# transmitter.net
KiCad netlist of a schematic drawn in EAGLE
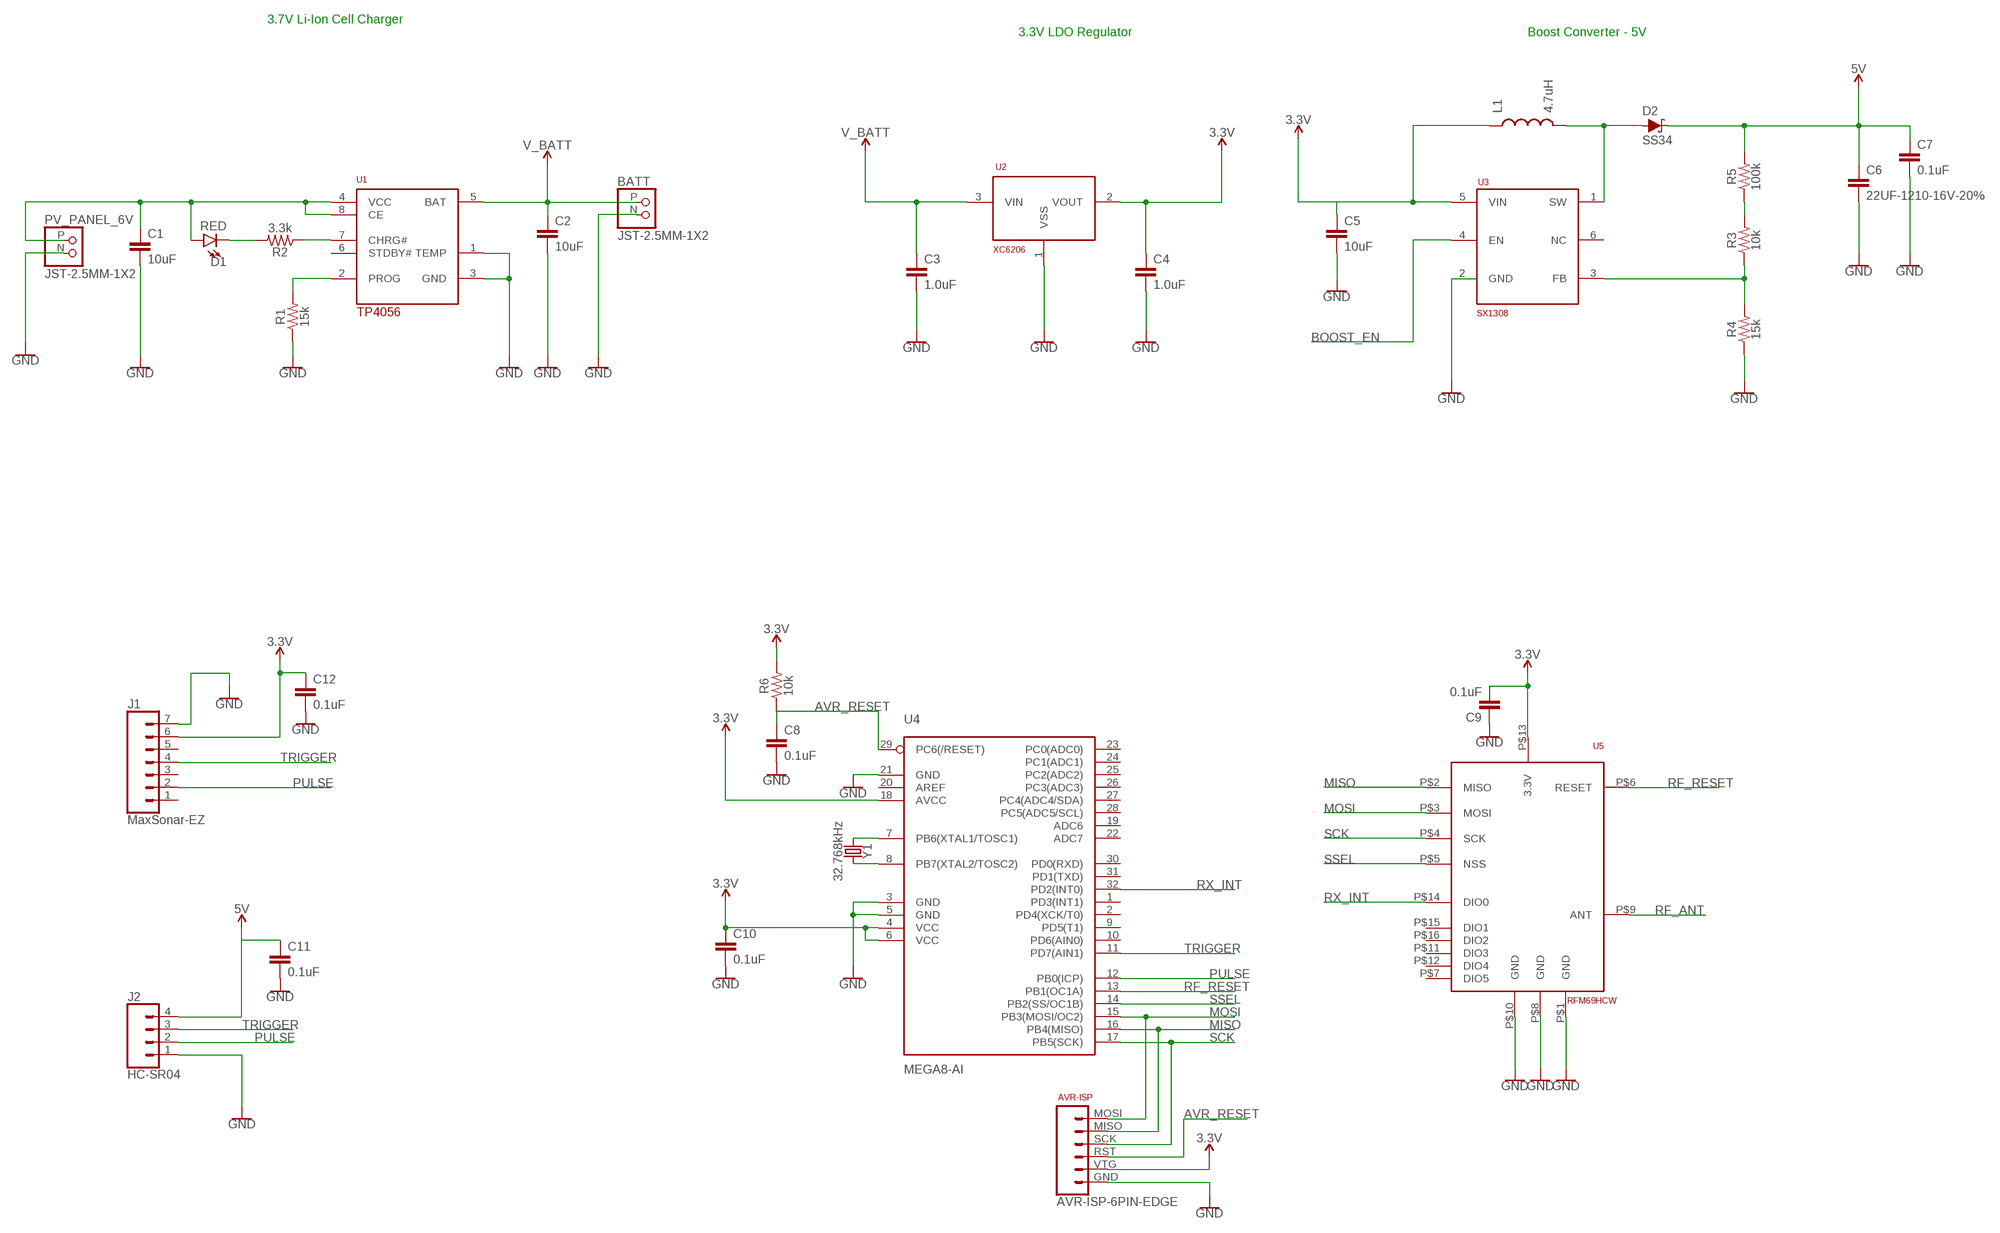
[diagram p0: schematic, sheet 1]

(export (version "E")
  (design (tool "Eeschema 10.0.6"))
  (components
    (comp (ref "BATT")
      (value "JST-2.5MM-1X2")
      (footprint "eagle-import:JST-2.5MM-1X2-THM")
      (libsource (lib "eagle-import") (part "JST-2.5MM-1X2"))
    )
    (comp (ref "C1")
      (value "10uF")
      (footprint "eagle-import:1206")
      (libsource (lib "eagle-import") (part "10UF-1206-6.3V-20%"))
    )
    (comp (ref "C2")
      (value "10uF")
      (footprint "eagle-import:1206")
      (libsource (lib "eagle-import") (part "10UF-1206-6.3V-20%"))
    )
    (comp (ref "C3")
      (value "1.0uF")
      (footprint "eagle-import:0603")
      (libsource (lib "eagle-import") (part "1.0UF-0603-16V-10%"))
    )
    (comp (ref "C4")
      (value "1.0uF")
      (footprint "eagle-import:0603")
      (libsource (lib "eagle-import") (part "1.0UF-0603-16V-10%"))
    )
    (comp (ref "C5")
      (value "10uF")
      (footprint "eagle-import:1206")
      (libsource (lib "eagle-import") (part "10UF-1206-6.3V-20%"))
    )
    (comp (ref "C6")
      (value "22UF-1210-16V-20%")
      (footprint "eagle-import:1210")
      (libsource (lib "eagle-import") (part "22UF-1210-16V-20%"))
    )
    (comp (ref "C7")
      (value "0.1uF")
      (footprint "eagle-import:0603")
      (libsource (lib "eagle-import") (part "0.1UF-0603-25V-5%"))
    )
    (comp (ref "C8")
      (value "0.1uF")
      (footprint "eagle-import:0603")
      (libsource (lib "eagle-import") (part "0.1UF-0603-25V-5%"))
    )
    (comp (ref "C9")
      (value "0.1uF")
      (footprint "eagle-import:0603")
      (libsource (lib "eagle-import") (part "0.1UF-0603-25V-(+80/-20%)"))
    )
    (comp (ref "C10")
      (value "0.1uF")
      (footprint "eagle-import:0603")
      (libsource (lib "eagle-import") (part "0.1UF-0603-25V-(+80/-20%)"))
    )
    (comp (ref "C11")
      (value "0.1uF")
      (footprint "eagle-import:0603")
      (libsource (lib "eagle-import") (part "0.1UF-0603-25V-(+80/-20%)"))
    )
    (comp (ref "C12")
      (value "0.1uF")
      (footprint "eagle-import:0603")
      (libsource (lib "eagle-import") (part "0.1UF-0603-25V-(+80/-20%)"))
    )
    (comp (ref "D1")
      (value "RED")
      (footprint "eagle-import:LED-1206")
      (libsource (lib "eagle-import") (part "LED-RED1206"))
    )
    (comp (ref "D2")
      (value "SS34")
      (footprint "eagle-import:SMA-DIODE")
      (libsource (lib "eagle-import") (part "DIODE-SCHOTTKY"))
    )
    (comp (ref "J1")
      (value "MaxSonar-EZ")
      (footprint "eagle-import:1X07")
      (libsource (lib "eagle-import") (part "CONN_07"))
    )
    (comp (ref "J2")
      (value "HC-SR04")
      (footprint "eagle-import:1X04")
      (libsource (lib "eagle-import") (part "CONN_04"))
    )
    (comp (ref "L1")
      (value "4.7uH")
      (footprint "eagle-import:SDR0403")
      (libsource (lib "eagle-import") (part "INDUCTOR3MM"))
    )
    (comp (ref "PV_PANEL_6V")
      (value "JST-2.5MM-1X2")
      (footprint "eagle-import:JST-2.5MM-1X2-THM")
      (libsource (lib "eagle-import") (part "JST-2.5MM-1X2"))
    )
    (comp (ref "R1")
      (value "15k")
      (footprint "eagle-import:0603")
      (libsource (lib "eagle-import") (part "15KOHM-0603-1/10W-1%"))
    )
    (comp (ref "R2")
      (value "3.3k")
      (footprint "eagle-import:0603")
      (libsource (lib "eagle-import") (part "3.3KOHM-0603-1/10W-1%"))
    )
    (comp (ref "R3")
      (value "10k")
      (footprint "eagle-import:0603")
      (libsource (lib "eagle-import") (part "10KOHM-0603-1/10W-1%"))
    )
    (comp (ref "R4")
      (value "15k")
      (footprint "eagle-import:0603")
      (libsource (lib "eagle-import") (part "15KOHM-0603-1/10W-1%"))
    )
    (comp (ref "R5")
      (value "100k")
      (footprint "eagle-import:0603")
      (libsource (lib "eagle-import") (part "100KOHM-0603-1/10W-1%"))
    )
    (comp (ref "R6")
      (value "10k")
      (footprint "eagle-import:0603")
      (libsource (lib "eagle-import") (part "10KOHM-0603-1/10W-1%"))
    )
    (comp (ref "U$3")
      (value "AVR-ISP-6PIN-EDGE")
      (footprint "eagle-import:AVR-6PIN-ISP-EDGE")
      (libsource (lib "eagle-import") (part "AVR-ISP-6PIN-EDGE"))
    )
    (comp (ref "U1")
      (value "TP4056")
      (footprint "eagle-import:SO08")
      (libsource (lib "eagle-import") (part "TP4056"))
    )
    (comp (ref "U2")
      (value "XC6206")
      (footprint "eagle-import:SOT23-3")
      (libsource (lib "eagle-import") (part "XC6206"))
    )
    (comp (ref "U3")
      (value "SX1308")
      (footprint "eagle-import:SOT23-6")
      (libsource (lib "eagle-import") (part "SX1308"))
    )
    (comp (ref "U4")
      (value "MEGA8-AI")
      (footprint "eagle-import:TQFP32-08")
      (fields (field (name "MPN") "ATMEGA8-16AU"))
      (libsource (lib "eagle-import") (part "MEGA8-AI"))
    )
    (comp (ref "U5")
      (value "RFM69HCW")
      (footprint "eagle-import:RFM69HCW")
      (libsource (lib "eagle-import") (part "RFM69HCW"))
    )
    (comp (ref "Y1")
      (value "32.768kHz")
      (footprint "eagle-import:CRYSTAL-PTH-2X6-CYL")
      (libsource (lib "eagle-import") (part "CRYSTAL-32.768KHZPTH-2X6"))
    )
  )
  (nets
    (net (code "1") (name "/AVR_RESET") (class "Default")
      (node (ref "C8") (pin "1") (pinfunction "1_1") (pintype "passive"))
      (node (ref "R6") (pin "1") (pinfunction "1_1") (pintype "passive"))
      (node (ref "U$3") (pin "RST") (pinfunction "RST_RST") (pintype "passive"))
      (node (ref "U4") (pin "29") (pinfunction "PC6(/RESET)_29") (pintype "bidirectional"))
    )
    (net (code "2") (name "/BOOST_EN") (class "Default")
      (node (ref "U3") (pin "4") (pinfunction "EN_4") (pintype "bidirectional"))
    )
    (net (code "3") (name "/MISO") (class "Default")
      (node (ref "U$3") (pin "MISO") (pinfunction "MISO_MISO") (pintype "passive"))
      (node (ref "U4") (pin "16") (pinfunction "PB4(MISO)_16") (pintype "bidirectional"))
      (node (ref "U5") (pin "P$2") (pinfunction "MISO_P$2") (pintype "bidirectional"))
    )
    (net (code "4") (name "/MOSI") (class "Default")
      (node (ref "U$3") (pin "MOSI") (pinfunction "MOSI_MOSI") (pintype "passive"))
      (node (ref "U4") (pin "15") (pinfunction "PB3(MOSI/OC2)_15") (pintype "bidirectional"))
      (node (ref "U5") (pin "P$3") (pinfunction "MOSI_P$3") (pintype "bidirectional"))
    )
    (net (code "5") (name "/PULSE") (class "Default")
      (node (ref "J1") (pin "2") (pinfunction "2_2") (pintype "passive"))
      (node (ref "J2") (pin "2") (pinfunction "2_2") (pintype "passive"))
      (node (ref "U4") (pin "12") (pinfunction "PB0(ICP)_12") (pintype "bidirectional"))
    )
    (net (code "6") (name "/RF_ANT") (class "Default")
      (node (ref "U5") (pin "P$9") (pinfunction "ANT_P$9") (pintype "bidirectional"))
    )
    (net (code "7") (name "/RF_RESET") (class "Default")
      (node (ref "U4") (pin "13") (pinfunction "PB1(OC1A)_13") (pintype "bidirectional"))
      (node (ref "U5") (pin "P$6") (pinfunction "RESET_P$6") (pintype "bidirectional"))
    )
    (net (code "8") (name "/RX_INT") (class "Default")
      (node (ref "U4") (pin "32") (pinfunction "PD2(INT0)_32") (pintype "bidirectional"))
      (node (ref "U5") (pin "P$14") (pinfunction "DIO0_P$14") (pintype "bidirectional"))
    )
    (net (code "9") (name "/SCK") (class "Default")
      (node (ref "U$3") (pin "SCK") (pinfunction "SCK_SCK") (pintype "passive"))
      (node (ref "U4") (pin "17") (pinfunction "PB5(SCK)_17") (pintype "bidirectional"))
      (node (ref "U5") (pin "P$4") (pinfunction "SCK_P$4") (pintype "bidirectional"))
    )
    (net (code "10") (name "/SSEL") (class "Default")
      (node (ref "U4") (pin "14") (pinfunction "PB2(SS/OC1B)_14") (pintype "bidirectional"))
      (node (ref "U5") (pin "P$5") (pinfunction "NSS_P$5") (pintype "bidirectional"))
    )
    (net (code "11") (name "/TRIGGER") (class "Default")
      (node (ref "J1") (pin "4") (pinfunction "4_4") (pintype "passive"))
      (node (ref "J2") (pin "3") (pinfunction "3_3") (pintype "passive"))
      (node (ref "U4") (pin "11") (pinfunction "PD7(AIN1)_11") (pintype "bidirectional"))
    )
    (net (code "12") (name "3.3V") (class "Default")
      (node (ref "C10") (pin "1") (pinfunction "1_1") (pintype "passive"))
      (node (ref "C12") (pin "1") (pinfunction "1_1") (pintype "passive"))
      (node (ref "C4") (pin "1") (pinfunction "1_1") (pintype "passive"))
      (node (ref "C5") (pin "1") (pinfunction "1_1") (pintype "passive"))
      (node (ref "C9") (pin "2") (pinfunction "2_2") (pintype "passive"))
      (node (ref "J1") (pin "6") (pinfunction "6_6") (pintype "passive"))
      (node (ref "L1") (pin "P$1") (pinfunction "1_P$1") (pintype "passive"))
      (node (ref "R6") (pin "2") (pinfunction "2_2") (pintype "passive"))
      (node (ref "U$3") (pin "VTG") (pinfunction "VTG_VTG") (pintype "passive"))
      (node (ref "U2") (pin "2") (pinfunction "VOUT_2") (pintype "bidirectional"))
      (node (ref "U3") (pin "5") (pinfunction "VIN_5") (pintype "bidirectional"))
      (node (ref "U4") (pin "18") (pinfunction "AVCC_18") (pintype "power_in"))
      (node (ref "U4") (pin "4") (pinfunction "VCC_4") (pintype "power_in"))
      (node (ref "U4") (pin "6") (pinfunction "VCC_6") (pintype "power_in"))
      (node (ref "U5") (pin "P$13") (pinfunction "3.3V_P$13") (pintype "power_in"))
    )
    (net (code "13") (name "5V") (class "Default")
      (node (ref "C11") (pin "1") (pinfunction "1_1") (pintype "passive"))
      (node (ref "C6") (pin "1") (pinfunction "1_1") (pintype "passive"))
      (node (ref "C7") (pin "1") (pinfunction "1_1") (pintype "passive"))
      (node (ref "D2") (pin "C") (pinfunction "C_C") (pintype "passive"))
      (node (ref "J2") (pin "4") (pinfunction "4_4") (pintype "passive"))
      (node (ref "R5") (pin "2") (pinfunction "2_2") (pintype "passive"))
    )
    (net (code "14") (name "GND") (class "Default")
      (node (ref "BATT") (pin "N") (pinfunction "N_N") (pintype "passive"))
      (node (ref "C1") (pin "2") (pinfunction "2_2") (pintype "passive"))
      (node (ref "C10") (pin "2") (pinfunction "2_2") (pintype "passive"))
      (node (ref "C11") (pin "2") (pinfunction "2_2") (pintype "passive"))
      (node (ref "C12") (pin "2") (pinfunction "2_2") (pintype "passive"))
      (node (ref "C2") (pin "2") (pinfunction "2_2") (pintype "passive"))
      (node (ref "C3") (pin "2") (pinfunction "2_2") (pintype "passive"))
      (node (ref "C4") (pin "2") (pinfunction "2_2") (pintype "passive"))
      (node (ref "C5") (pin "2") (pinfunction "2_2") (pintype "passive"))
      (node (ref "C6") (pin "2") (pinfunction "2_2") (pintype "passive"))
      (node (ref "C7") (pin "2") (pinfunction "2_2") (pintype "passive"))
      (node (ref "C8") (pin "2") (pinfunction "2_2") (pintype "passive"))
      (node (ref "C9") (pin "1") (pinfunction "1_1") (pintype "passive"))
      (node (ref "J1") (pin "7") (pinfunction "7_7") (pintype "passive"))
      (node (ref "J2") (pin "1") (pinfunction "1_1") (pintype "passive"))
      (node (ref "PV_PANEL_6V") (pin "N") (pinfunction "N_N") (pintype "passive"))
      (node (ref "R1") (pin "1") (pinfunction "1_1") (pintype "passive"))
      (node (ref "R4") (pin "1") (pinfunction "1_1") (pintype "passive"))
      (node (ref "U$3") (pin "GND") (pinfunction "GND_GND") (pintype "passive"))
      (node (ref "U1") (pin "1") (pinfunction "TEMP_1") (pintype "bidirectional"))
      (node (ref "U1") (pin "3") (pinfunction "GND_3") (pintype "bidirectional"))
      (node (ref "U2") (pin "1") (pinfunction "VSS_1") (pintype "bidirectional"))
      (node (ref "U3") (pin "2") (pinfunction "GND_2") (pintype "bidirectional"))
      (node (ref "U4") (pin "21") (pinfunction "GND_21") (pintype "power_in"))
      (node (ref "U4") (pin "3") (pinfunction "GND_3") (pintype "power_in"))
      (node (ref "U4") (pin "5") (pinfunction "GND_5") (pintype "power_in"))
      (node (ref "U5") (pin "P$1") (pinfunction "GND_P$1") (pintype "power_in"))
      (node (ref "U5") (pin "P$10") (pinfunction "GND_P$10") (pintype "power_in"))
      (node (ref "U5") (pin "P$8") (pinfunction "GND_P$8") (pintype "power_in"))
    )
    (net (code "15") (name "Net-(D1-PadC)") (class "Default")
      (node (ref "D1") (pin "C") (pinfunction "C_C") (pintype "passive"))
      (node (ref "R2") (pin "2") (pinfunction "2_2") (pintype "passive"))
    )
    (net (code "16") (name "Net-(L1-2)") (class "Default")
      (node (ref "D2") (pin "A") (pinfunction "A_A") (pintype "passive"))
      (node (ref "L1") (pin "P$2") (pinfunction "2_P$2") (pintype "passive"))
      (node (ref "U3") (pin "1") (pinfunction "SW_1") (pintype "bidirectional"))
    )
    (net (code "17") (name "Net-(R3-Pad2)") (class "Default")
      (node (ref "R3") (pin "2") (pinfunction "2_2") (pintype "passive"))
      (node (ref "R5") (pin "1") (pinfunction "1_1") (pintype "passive"))
    )
    (net (code "18") (name "Net-(U1-CE)") (class "Default")
      (node (ref "C1") (pin "1") (pinfunction "1_1") (pintype "passive"))
      (node (ref "D1") (pin "A") (pinfunction "A_A") (pintype "passive"))
      (node (ref "PV_PANEL_6V") (pin "P") (pinfunction "P_P") (pintype "passive"))
      (node (ref "U1") (pin "4") (pinfunction "VCC_4") (pintype "bidirectional"))
      (node (ref "U1") (pin "8") (pinfunction "CE_8") (pintype "bidirectional"))
    )
    (net (code "19") (name "Net-(U1-CHRG#)") (class "Default")
      (node (ref "R2") (pin "1") (pinfunction "1_1") (pintype "passive"))
      (node (ref "U1") (pin "7") (pinfunction "CHRG#_7") (pintype "bidirectional"))
    )
    (net (code "20") (name "Net-(U1-PROG)") (class "Default")
      (node (ref "R1") (pin "2") (pinfunction "2_2") (pintype "passive"))
      (node (ref "U1") (pin "2") (pinfunction "PROG_2") (pintype "bidirectional"))
    )
    (net (code "21") (name "Net-(U3-FB)") (class "Default")
      (node (ref "R3") (pin "1") (pinfunction "1_1") (pintype "passive"))
      (node (ref "R4") (pin "2") (pinfunction "2_2") (pintype "passive"))
      (node (ref "U3") (pin "3") (pinfunction "FB_3") (pintype "bidirectional"))
    )
    (net (code "22") (name "Net-(U4-PB6(XTAL1{slash}TOSC1))") (class "Default")
      (node (ref "U4") (pin "7") (pinfunction "PB6(XTAL1/TOSC1)_7") (pintype "bidirectional"))
      (node (ref "Y1") (pin "1") (pinfunction "1_1") (pintype "passive"))
    )
    (net (code "23") (name "Net-(U4-PB7(XTAL2{slash}TOSC2))") (class "Default")
      (node (ref "U4") (pin "8") (pinfunction "PB7(XTAL2/TOSC2)_8") (pintype "bidirectional"))
      (node (ref "Y1") (pin "2") (pinfunction "2_2") (pintype "passive"))
    )
    (net (code "24") (name "V_BATT") (class "Default")
      (node (ref "BATT") (pin "P") (pinfunction "P_P") (pintype "passive"))
      (node (ref "C2") (pin "1") (pinfunction "1_1") (pintype "passive"))
      (node (ref "C3") (pin "1") (pinfunction "1_1") (pintype "passive"))
      (node (ref "U1") (pin "5") (pinfunction "BAT_5") (pintype "bidirectional"))
      (node (ref "U2") (pin "3") (pinfunction "VIN_3") (pintype "bidirectional"))
    )
    (net (code "25") (name "unconnected-(J1-Pad1)") (class "Default")
      (node (ref "J1") (pin "1") (pinfunction "1_1") (pintype "passive"))
    )
    (net (code "26") (name "unconnected-(J1-Pad3)") (class "Default")
      (node (ref "J1") (pin "3") (pinfunction "3_3") (pintype "passive"))
    )
    (net (code "27") (name "unconnected-(J1-Pad5)") (class "Default")
      (node (ref "J1") (pin "5") (pinfunction "5_5") (pintype "passive"))
    )
    (net (code "28") (name "unconnected-(U1-STDBY#-Pad6)") (class "Default")
      (node (ref "U1") (pin "6") (pinfunction "STDBY#_6") (pintype "bidirectional"))
    )
    (net (code "29") (name "unconnected-(U3-NC-Pad6)") (class "Default")
      (node (ref "U3") (pin "6") (pinfunction "NC_6") (pintype "bidirectional"))
    )
    (net (code "30") (name "unconnected-(U4-ADC6-Pad19)") (class "Default")
      (node (ref "U4") (pin "19") (pinfunction "ADC6_19") (pintype "bidirectional"))
    )
    (net (code "31") (name "unconnected-(U4-ADC7-Pad22)") (class "Default")
      (node (ref "U4") (pin "22") (pinfunction "ADC7_22") (pintype "bidirectional"))
    )
    (net (code "32") (name "unconnected-(U4-AREF-Pad20)") (class "Default")
      (node (ref "U4") (pin "20") (pinfunction "AREF_20") (pintype "passive"))
    )
    (net (code "33") (name "unconnected-(U4-PC0(ADC0)-Pad23)") (class "Default")
      (node (ref "U4") (pin "23") (pinfunction "PC0(ADC0)_23") (pintype "bidirectional"))
    )
    (net (code "34") (name "unconnected-(U4-PC1(ADC1)-Pad24)") (class "Default")
      (node (ref "U4") (pin "24") (pinfunction "PC1(ADC1)_24") (pintype "bidirectional"))
    )
    (net (code "35") (name "unconnected-(U4-PC2(ADC2)-Pad25)") (class "Default")
      (node (ref "U4") (pin "25") (pinfunction "PC2(ADC2)_25") (pintype "bidirectional"))
    )
    (net (code "36") (name "unconnected-(U4-PC3(ADC3)-Pad26)") (class "Default")
      (node (ref "U4") (pin "26") (pinfunction "PC3(ADC3)_26") (pintype "bidirectional"))
    )
    (net (code "37") (name "unconnected-(U4-PC4(ADC4{slash}SDA)-Pad27)") (class "Default")
      (node (ref "U4") (pin "27") (pinfunction "PC4(ADC4/SDA)_27") (pintype "bidirectional"))
    )
    (net (code "38") (name "unconnected-(U4-PC5(ADC5{slash}SCL)-Pad28)") (class "Default")
      (node (ref "U4") (pin "28") (pinfunction "PC5(ADC5/SCL)_28") (pintype "bidirectional"))
    )
    (net (code "39") (name "unconnected-(U4-PD0(RXD)-Pad30)") (class "Default")
      (node (ref "U4") (pin "30") (pinfunction "PD0(RXD)_30") (pintype "bidirectional"))
    )
    (net (code "40") (name "unconnected-(U4-PD1(TXD)-Pad31)") (class "Default")
      (node (ref "U4") (pin "31") (pinfunction "PD1(TXD)_31") (pintype "bidirectional"))
    )
    (net (code "41") (name "unconnected-(U4-PD3(INT1)-Pad1)") (class "Default")
      (node (ref "U4") (pin "1") (pinfunction "PD3(INT1)_1") (pintype "bidirectional"))
    )
    (net (code "42") (name "unconnected-(U4-PD4(XCK{slash}T0)-Pad2)") (class "Default")
      (node (ref "U4") (pin "2") (pinfunction "PD4(XCK/T0)_2") (pintype "bidirectional"))
    )
    (net (code "43") (name "unconnected-(U4-PD5(T1)-Pad9)") (class "Default")
      (node (ref "U4") (pin "9") (pinfunction "PD5(T1)_9") (pintype "bidirectional"))
    )
    (net (code "44") (name "unconnected-(U4-PD6(AIN0)-Pad10)") (class "Default")
      (node (ref "U4") (pin "10") (pinfunction "PD6(AIN0)_10") (pintype "bidirectional"))
    )
    (net (code "45") (name "unconnected-(U5-DIO1-PadP$15)") (class "Default")
      (node (ref "U5") (pin "P$15") (pinfunction "DIO1_P$15") (pintype "bidirectional"))
    )
    (net (code "46") (name "unconnected-(U5-DIO2-PadP$16)") (class "Default")
      (node (ref "U5") (pin "P$16") (pinfunction "DIO2_P$16") (pintype "bidirectional"))
    )
    (net (code "47") (name "unconnected-(U5-DIO3-PadP$11)") (class "Default")
      (node (ref "U5") (pin "P$11") (pinfunction "DIO3_P$11") (pintype "bidirectional"))
    )
    (net (code "48") (name "unconnected-(U5-DIO4-PadP$12)") (class "Default")
      (node (ref "U5") (pin "P$12") (pinfunction "DIO4_P$12") (pintype "bidirectional"))
    )
    (net (code "49") (name "unconnected-(U5-DIO5-PadP$7)") (class "Default")
      (node (ref "U5") (pin "P$7") (pinfunction "DIO5_P$7") (pintype "bidirectional"))
    )
  )
)
